# SCH_New-Project_2024-10-10.net
KiCad netlist of a schematic drawn in EasyEDA
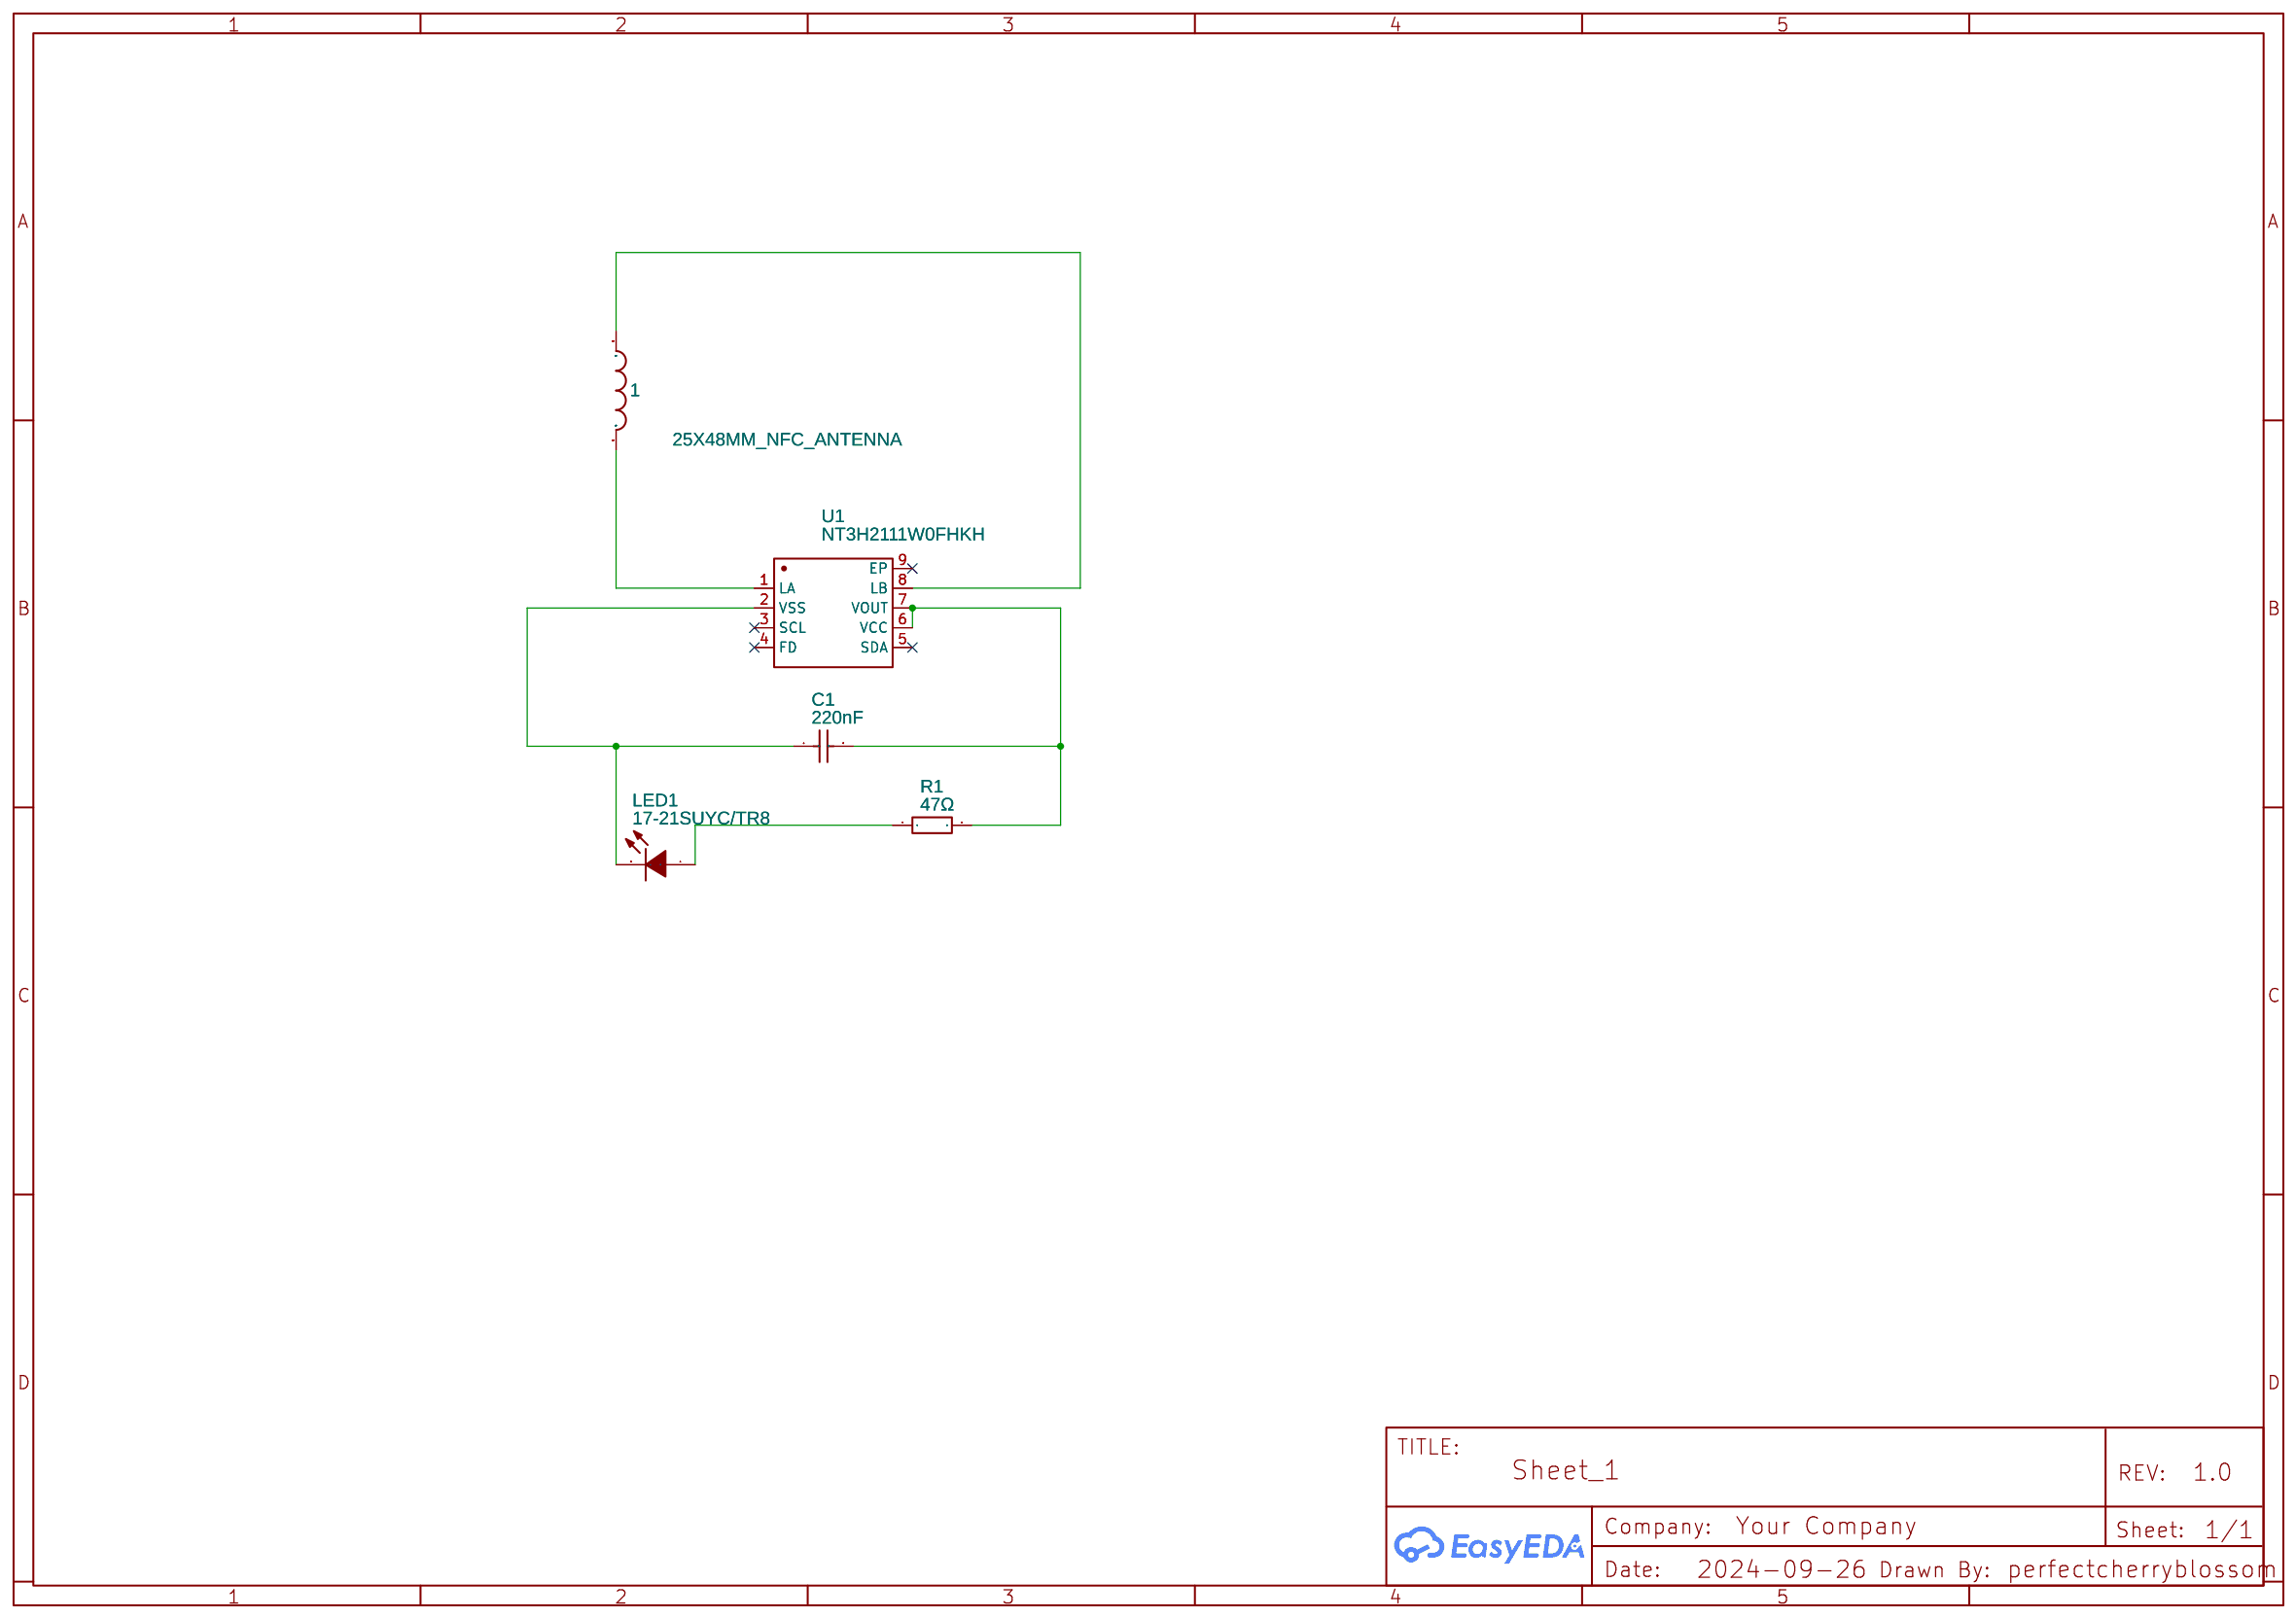
[diagram p0: schematic sheet]

(export (version "E")
  (design (tool "Eeschema 10.0.6"))
  (components
    (comp (ref "1") (value "25X48MM_NFC_ANTENNA") (libsource (lib "") (part "25X48MM_NFC_ANTENNA")))
    (comp (ref "C1")
      (value "220nF")
      (fields
        (field (name "Manufacturer Part") "CL10B224KA8NNNC")
        (field (name "Manufacturer") "SAMSUNG(三星)")
      )
      (libsource (lib "") (part "CL10B224KA8NNNC"))
    )
    (comp (ref "LED1")
      (value "17-21SUYC/TR8")
      (fields (field (name "Manufacturer Part") "KT-0805黄灯") (field (name "Manufacturer") "KENTO"))
      (libsource (lib "") (part "17-21SUYC/TR8"))
    )
    (comp (ref "R1")
      (value "47Ω")
      (fields
        (field (name "Manufacturer Part") "0603WAF470JT5E")
        (field (name "Manufacturer") "UNI-ROYAL(厚声)")
      )
      (libsource (lib "") (part "0603WAF470JT5E"))
    )
    (comp (ref "U1")
      (value "NT3H2111W0FHKH")
      (fields (field (name "Manufacturer") "NXP(恩智浦)"))
      (libsource (lib "") (part "NT3H2111W0FHKH"))
    )
  )
  (nets
    (net (code "1") (name "Net-(LED1-+)") (class "Default")
      (node (ref "LED1") (pin "1") (pinfunction "+_1") (pintype "unspecified"))
      (node (ref "R1") (pin "1") (pinfunction "1_1") (pintype "input"))
    )
    (net (code "2") (name "Net-(LED1--)") (class "Default")
      (node (ref "C1") (pin "1") (pinfunction "1_1") (pintype "input"))
      (node (ref "LED1") (pin "2") (pinfunction "-_2") (pintype "unspecified"))
      (node (ref "U1") (pin "2") (pinfunction "VSS_2") (pintype "unspecified"))
    )
    (net (code "3") (name "Net-(U1-LA)") (class "Default")
      (node (ref "1") (pin "P$2") (pinfunction "P$2_P$2") (pintype "bidirectional"))
      (node (ref "U1") (pin "1") (pinfunction "LA_1") (pintype "unspecified"))
    )
    (net (code "4") (name "Net-(U1-LB)") (class "Default")
      (node (ref "1") (pin "P$1") (pinfunction "P$1_P$1") (pintype "bidirectional"))
      (node (ref "U1") (pin "8") (pinfunction "LB_8") (pintype "unspecified"))
    )
    (net (code "5") (name "Net-(U1-VCC)") (class "Default")
      (node (ref "C1") (pin "2") (pinfunction "2_2") (pintype "input"))
      (node (ref "R1") (pin "2") (pinfunction "2_2") (pintype "input"))
      (node (ref "U1") (pin "6") (pinfunction "VCC_6") (pintype "unspecified"))
      (node (ref "U1") (pin "7") (pinfunction "VOUT_7") (pintype "unspecified"))
    )
    (net (code "6") (name "unconnected-(U1-EP-Pad9)") (class "Default")
      (node (ref "U1") (pin "9") (pinfunction "EP_9") (pintype "unspecified+no_connect"))
    )
    (net (code "7") (name "unconnected-(U1-FD-Pad4)") (class "Default")
      (node (ref "U1") (pin "4") (pinfunction "FD_4") (pintype "unspecified+no_connect"))
    )
    (net (code "8") (name "unconnected-(U1-SCL-Pad3)") (class "Default")
      (node (ref "U1") (pin "3") (pinfunction "SCL_3") (pintype "unspecified+no_connect"))
    )
    (net (code "9") (name "unconnected-(U1-SDA-Pad5)") (class "Default")
      (node (ref "U1") (pin "5") (pinfunction "SDA_5") (pintype "unspecified+no_connect"))
    )
  )
)
